# DWM1000.net
KiCad netlist of a schematic drawn in Altium Designer
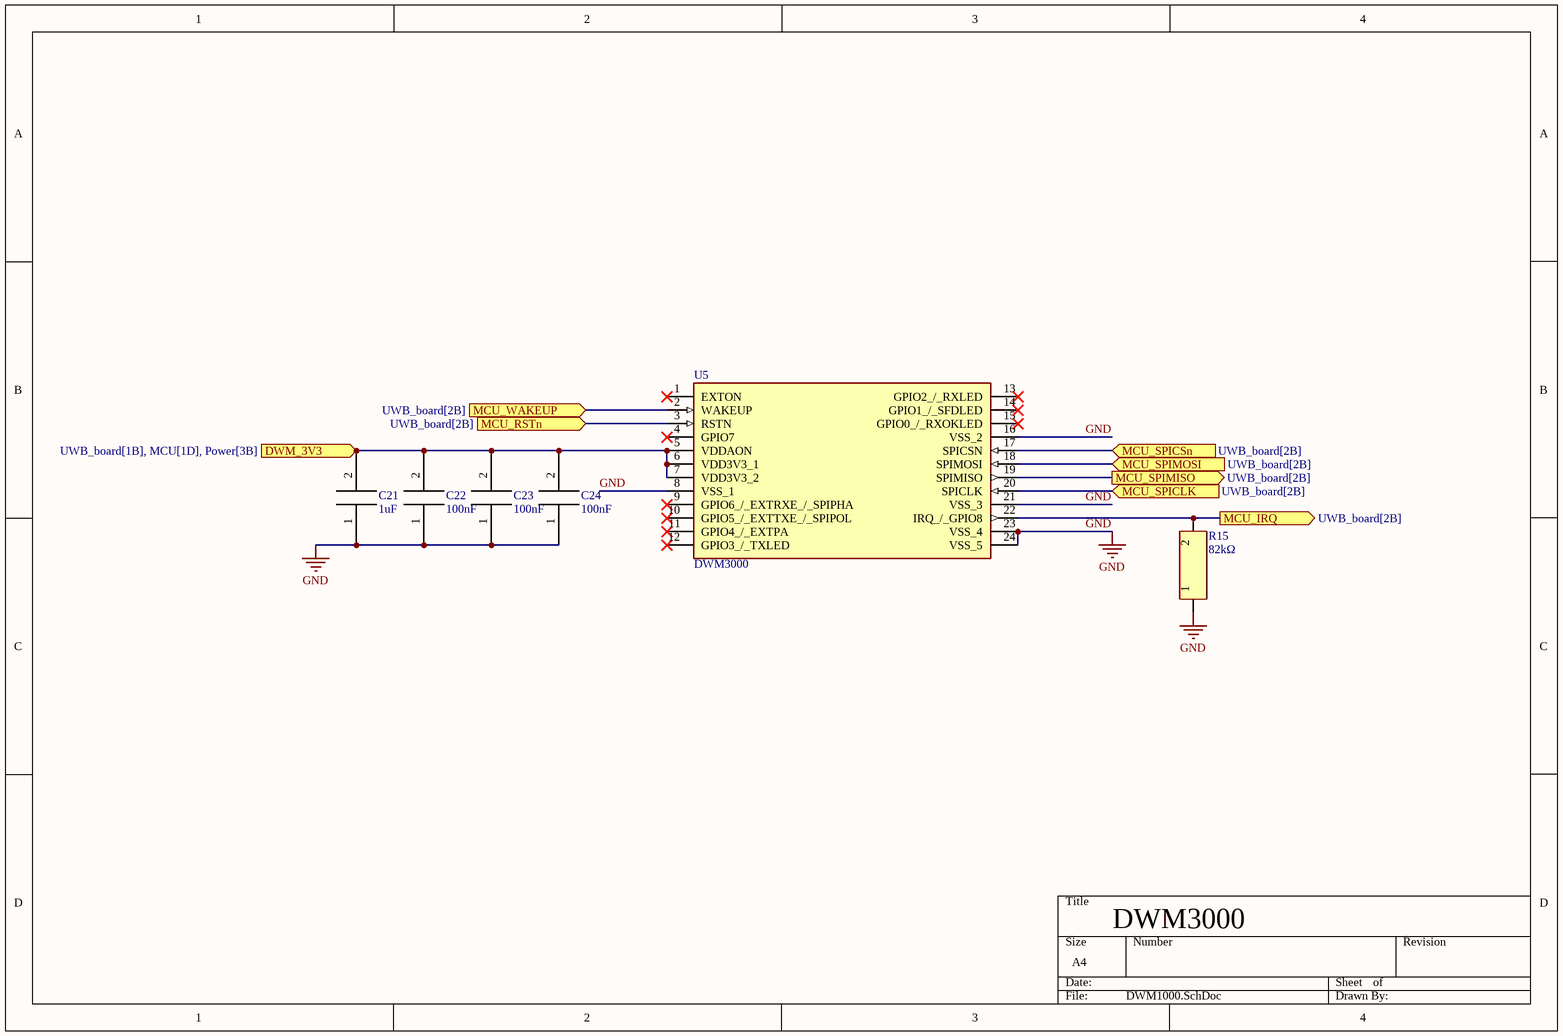
[diagram p0: DWM1000.SchDoc]

(export (version "E")
  (design (tool "Eeschema 10.0.6"))
  (components
    (comp (ref "C21")
      (value "1uF")
      (footprint "0603_cap")
      (description "1uF 50V X5R ±10% 0603 Multilayer Ceramic Capacitors MLCC - SMD/SMT ROHS")
      (fields (field (name "LCSC PART #") "C15849"))
      (libsource (lib "Schlib1") (part "CL10A105KB8NNNC"))
    )
    (comp (ref "C22")
      (value "100nF")
      (footprint "0603_cap")
      (description "100nF 50V X7R ±10% 0603 Multilayer Ceramic Capacitors MLCC - SMD/SMT ROHS")
      (fields (field (name "LCSC PART #") "C14663"))
      (libsource (lib "Schlib1") (part "CC0603KRX7R9BB104"))
    )
    (comp (ref "C23")
      (value "100nF")
      (footprint "0603_cap")
      (description "100nF 50V X7R ±10% 0603 Multilayer Ceramic Capacitors MLCC - SMD/SMT ROHS")
      (fields (field (name "LCSC PART #") "C14663"))
      (libsource (lib "Schlib1") (part "CC0603KRX7R9BB104"))
    )
    (comp (ref "C24")
      (value "100nF")
      (footprint "0603_cap")
      (description "100nF 50V X7R ±10% 0603 Multilayer Ceramic Capacitors MLCC - SMD/SMT ROHS")
      (fields (field (name "LCSC PART #") "C14663"))
      (libsource (lib "Schlib1") (part "CC0603KRX7R9BB104"))
    )
    (comp (ref "R15")
      (value "82kΩ")
      (footprint "0603_res")
      (fields (field (name "LCSC PART #") "C23254") (field (name "Comment") "82k"))
      (libsource (lib "Schlib1") (part "0603WAF8202T5E"))
    )
    (comp (ref "U5")
      (value "DWM3000")
      (footprint "DWM1000")
      (description "3.5 - 6.5 GHz Ultra-Wideband (UWB) Transceiver Module")
      (fields
        (field (name "MOUSER PART NUMBER") "772-DWM1000")
        (field (name "MANUFACTURER_PART_NUMBER") "DWM1000")
      )
      (libsource (lib "Schlib1") (part "DWM1000"))
    )
  )
  (nets
    (net (code "1") (name "/DWM_3V3") (class "Default")
      (node (ref "C21") (pin "2") (pinfunction "3_2") (pintype "passive"))
      (node (ref "C22") (pin "2") (pinfunction "3_2") (pintype "passive"))
      (node (ref "C23") (pin "2") (pinfunction "3_2") (pintype "passive"))
      (node (ref "C24") (pin "2") (pinfunction "3_2") (pintype "passive"))
      (node (ref "U5") (pin "5") (pinfunction "VDDAON_5") (pintype "passive"))
      (node (ref "U5") (pin "6") (pinfunction "VDD3V3_1_6") (pintype "passive"))
      (node (ref "U5") (pin "7") (pinfunction "VDD3V3_2_7") (pintype "passive"))
    )
    (net (code "2") (name "/MCU_IRQ") (class "Default")
      (node (ref "R15") (pin "2") (pinfunction "3_2") (pintype "passive"))
      (node (ref "U5") (pin "22") (pinfunction "IRQ_/_GPIO8_22") (pintype "output"))
    )
    (net (code "3") (name "/MCU_RSTn") (class "Default")
      (node (ref "U5") (pin "3") (pinfunction "RSTN_3") (pintype "input"))
    )
    (net (code "4") (name "/MCU_SPICLK") (class "Default")
      (node (ref "U5") (pin "20") (pinfunction "SPICLK_20") (pintype "input"))
    )
    (net (code "5") (name "/MCU_SPICSn") (class "Default")
      (node (ref "U5") (pin "17") (pinfunction "SPICSN_17") (pintype "input"))
    )
    (net (code "6") (name "/MCU_SPIMISO") (class "Default")
      (node (ref "U5") (pin "19") (pinfunction "SPIMISO_19") (pintype "output"))
    )
    (net (code "7") (name "/MCU_SPIMOSI") (class "Default")
      (node (ref "U5") (pin "18") (pinfunction "SPIMOSI_18") (pintype "input"))
    )
    (net (code "8") (name "/MCU_WAKEUP") (class "Default")
      (node (ref "U5") (pin "2") (pinfunction "WAKEUP_2") (pintype "input"))
    )
    (net (code "9") (name "GND") (class "Default")
      (node (ref "C21") (pin "1") (pintype "passive"))
      (node (ref "C22") (pin "1") (pintype "passive"))
      (node (ref "C23") (pin "1") (pintype "passive"))
      (node (ref "C24") (pin "1") (pintype "passive"))
      (node (ref "R15") (pin "1") (pinfunction "1_1") (pintype "passive"))
      (node (ref "U5") (pin "16") (pinfunction "VSS_2_16") (pintype "passive"))
      (node (ref "U5") (pin "21") (pinfunction "VSS_3_21") (pintype "passive"))
      (node (ref "U5") (pin "23") (pinfunction "VSS_4_23") (pintype "passive"))
      (node (ref "U5") (pin "24") (pinfunction "VSS_5_24") (pintype "passive"))
      (node (ref "U5") (pin "8") (pinfunction "VSS_1_8") (pintype "passive"))
    )
    (net (code "10") (name "unconnected-(U5-EXTON-Pad1)") (class "Default")
      (node (ref "U5") (pin "1") (pinfunction "EXTON_1") (pintype "passive+no_connect"))
    )
    (net (code "11") (name "unconnected-(U5-GPIO0_{slash}_RXOKLED-Pad15)") (class "Default")
      (node (ref "U5") (pin "15") (pinfunction "GPIO0_/_RXOKLED_15") (pintype "passive+no_connect"))
    )
    (net (code "12") (name "unconnected-(U5-GPIO1_{slash}_SFDLED-Pad14)") (class "Default")
      (node (ref "U5") (pin "14") (pinfunction "GPIO1_/_SFDLED_14") (pintype "passive+no_connect"))
    )
    (net (code "13") (name "unconnected-(U5-GPIO2_{slash}_RXLED-Pad13)") (class "Default")
      (node (ref "U5") (pin "13") (pinfunction "GPIO2_/_RXLED_13") (pintype "passive+no_connect"))
    )
    (net (code "14") (name "unconnected-(U5-GPIO3_{slash}_TXLED-Pad12)") (class "Default")
      (node (ref "U5") (pin "12") (pinfunction "GPIO3_/_TXLED_12") (pintype "passive+no_connect"))
    )
    (net (code "15") (name "unconnected-(U5-GPIO4_{slash}_EXTPA-Pad11)") (class "Default")
      (node (ref "U5") (pin "11") (pinfunction "GPIO4_/_EXTPA_11") (pintype "passive+no_connect"))
    )
    (net (code "16") (name "unconnected-(U5-GPIO5_{slash}_EXTTXE_{slash}_SPIPOL-Pad10)") (class "Default")
      (node (ref "U5") (pin "10") (pinfunction "GPIO5_/_EXTTXE_/_SPIPOL_10") (pintype "passive+no_connect"))
    )
    (net (code "17") (name "unconnected-(U5-GPIO6_{slash}_EXTRXE_{slash}_SPIPHA-Pad9)") (class "Default")
      (node (ref "U5") (pin "9") (pinfunction "GPIO6_/_EXTRXE_/_SPIPHA_9") (pintype "passive+no_connect"))
    )
    (net (code "18") (name "unconnected-(U5-GPIO7-Pad4)") (class "Default")
      (node (ref "U5") (pin "4") (pinfunction "GPIO7_4") (pintype "passive+no_connect"))
    )
  )
)
